# soldererboutdisplay.net
KiCad netlist of a schematic drawn in Altium Designer
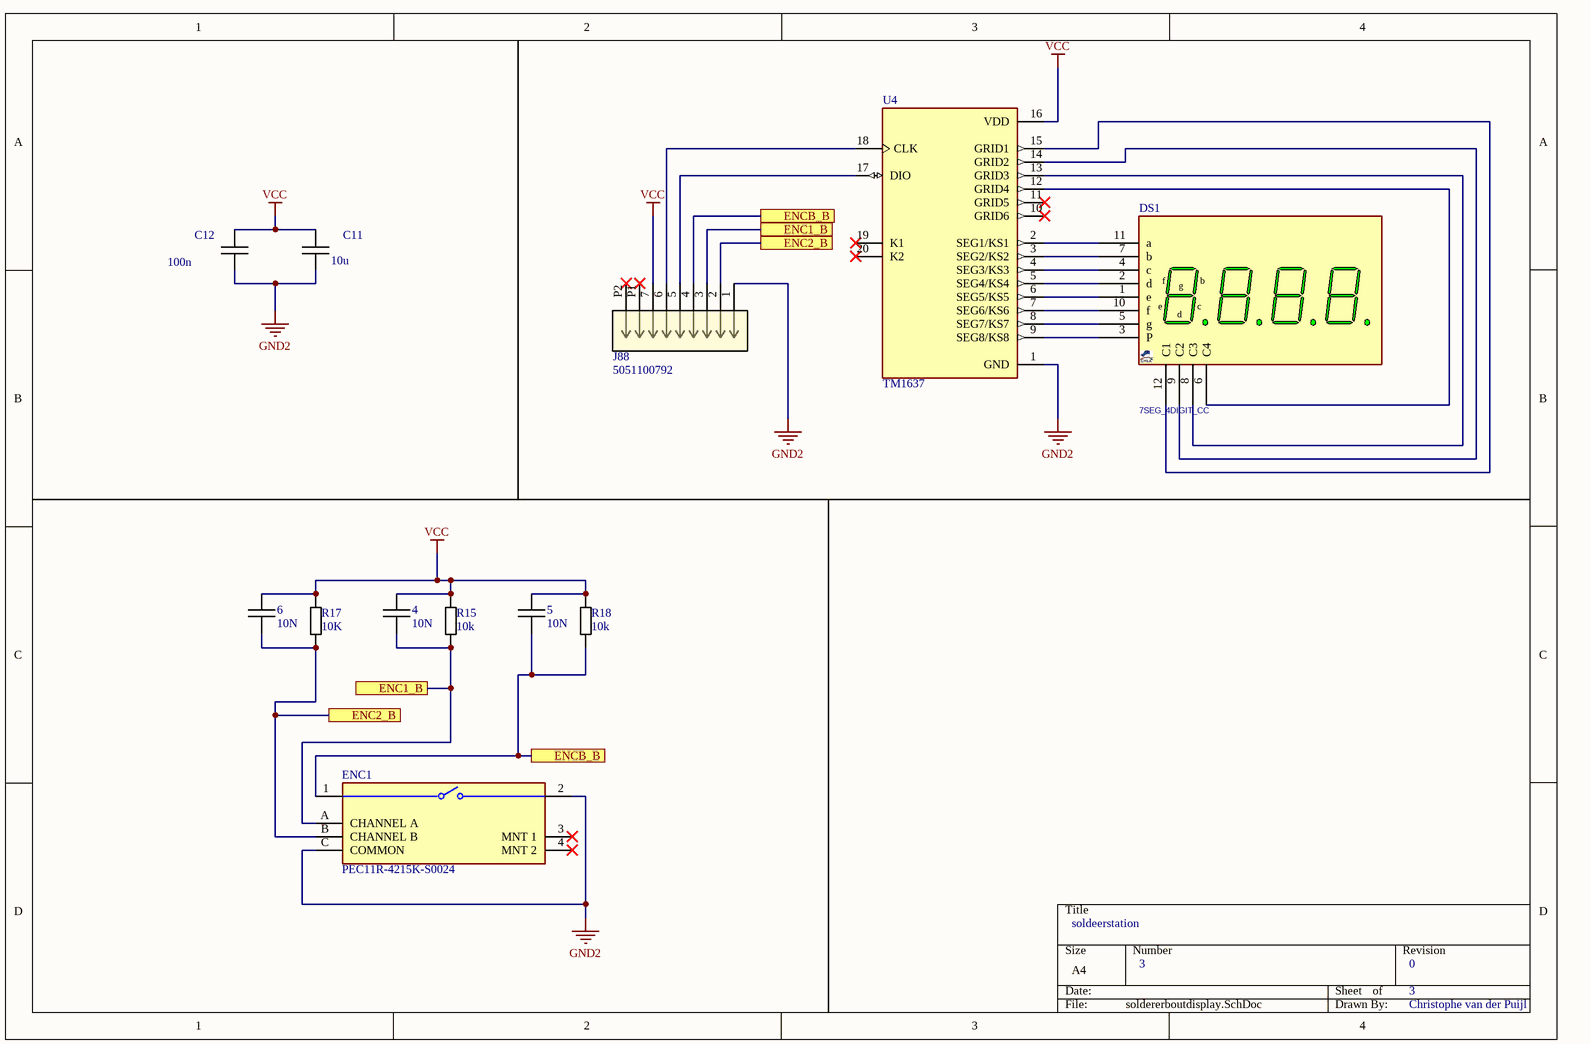
[diagram p0: soldererboutdisplay.SchDoc]

(export (version "E")
  (design (tool "Eeschema 10.0.6"))
  (components
    (comp (ref "4") (value "10N") (footprint "C 0603 / 1608") (libsource (lib "Standard") (part "Capacitor")))
    (comp (ref "5") (value "10N") (footprint "C 0603 / 1608") (libsource (lib "Standard") (part "Capacitor")))
    (comp (ref "6") (value "10N") (footprint "C 0603 / 1608") (libsource (lib "Standard") (part "Capacitor")))
    (comp (ref "C11")
      (value "10u")
      (footprint "C 0603 / 1608")
      (libsource (lib "Standard") (part "Capacitor"))
    )
    (comp (ref "C12")
      (value "100n")
      (footprint "C 0603 / 1608")
      (libsource (lib "Standard") (part "Capacitor"))
    )
    (comp (ref "DS1")
      (value "7SEG_4DIGIT_CC")
      (footprint "7SEGX4_12")
      (description "7SEGMENT, 4DIGIT, common cathode 5641")
      (fields (field (name "MANF_P#") "DPY-4CK"))
      (libsource (lib "Standard") (part "7SEG_4DIGIT_CC"))
    )
    (comp (ref "ENC1")
      (value "PEC11R-4215K-S0024")
      (footprint "FP-PEC11R-4215K-S0024-MFG")
      (description "ROTARY ENCODER MECHANICAL 24PPR")
      (libsource (lib "Standard") (part "pec11r425fs0024"))
    )
    (comp (ref "J88")
      (value "5051100792")
      (footprint "CON_5051100792_MOL")
      (description "No Description Available")
      (libsource (lib "Standard") (part "5051100792"))
    )
    (comp (ref "R15") (value "10k") (footprint "R 0603") (libsource (lib "Standard") (part "Resistor")))
    (comp (ref "R17") (value "10K") (footprint "R 0603") (libsource (lib "Standard") (part "Resistor")))
    (comp (ref "R18") (value "10k") (footprint "R 0603") (libsource (lib "Standard") (part "Resistor")))
    (comp (ref "U4")
      (value "TM1637")
      (footprint "DIP778W43P254L2612H431Q20N")
      (description "LED Drive Control Special Circuit")
      (fields (field (name "MF") "Titan Micro Electronics"))
      (libsource (lib "Standard") (part "TM1637"))
    )
  )
  (nets
    (net (code "1") (name "/ENC1_B") (class "Default")
      (node (ref "4") (pin "1") (pinfunction "1_1") (pintype "passive"))
      (node (ref "ENC1") (pin "A") (pinfunction "CHANNEL_A_A") (pintype "passive"))
      (node (ref "J88") (pin "3") (pinfunction "3_3") (pintype "passive"))
      (node (ref "R15") (pin "1") (pinfunction "1_1") (pintype "passive"))
    )
    (net (code "2") (name "/ENC2_B") (class "Default")
      (node (ref "6") (pin "1") (pinfunction "1_1") (pintype "passive"))
      (node (ref "ENC1") (pin "B") (pinfunction "CHANNEL_B_B") (pintype "passive"))
      (node (ref "J88") (pin "2") (pinfunction "2_2") (pintype "passive"))
      (node (ref "R17") (pin "1") (pinfunction "1_1") (pintype "passive"))
    )
    (net (code "3") (name "/ENCB_B") (class "Default")
      (node (ref "5") (pin "1") (pinfunction "1_1") (pintype "passive"))
      (node (ref "ENC1") (pin "1") (pinfunction "1_1") (pintype "passive"))
      (node (ref "J88") (pin "4") (pinfunction "4_4") (pintype "passive"))
      (node (ref "R18") (pin "1") (pinfunction "1_1") (pintype "passive"))
    )
    (net (code "4") (name "GND2") (class "Default")
      (node (ref "C11") (pin "2") (pinfunction "1_2") (pintype "passive"))
      (node (ref "C12") (pin "2") (pinfunction "1_2") (pintype "passive"))
      (node (ref "ENC1") (pin "2") (pinfunction "2_2") (pintype "passive"))
      (node (ref "ENC1") (pin "C") (pinfunction "COMMON_C") (pintype "passive"))
      (node (ref "J88") (pin "1") (pinfunction "1_1") (pintype "passive"))
      (node (ref "U4") (pin "1") (pinfunction "GND_1") (pintype "power_in"))
    )
    (net (code "5") (name "Net-(DS1-C1)") (class "Default")
      (node (ref "DS1") (pin "12") (pinfunction "C1_12") (pintype "passive"))
      (node (ref "U4") (pin "15") (pinfunction "GRID1_15") (pintype "output"))
    )
    (net (code "6") (name "Net-(DS1-C2)") (class "Default")
      (node (ref "DS1") (pin "9") (pinfunction "C2_9") (pintype "passive"))
      (node (ref "U4") (pin "14") (pinfunction "GRID2_14") (pintype "output"))
    )
    (net (code "7") (name "Net-(DS1-C3)") (class "Default")
      (node (ref "DS1") (pin "8") (pinfunction "C3_8") (pintype "passive"))
      (node (ref "U4") (pin "13") (pinfunction "GRID3_13") (pintype "output"))
    )
    (net (code "8") (name "Net-(DS1-C4)") (class "Default")
      (node (ref "DS1") (pin "6") (pinfunction "C4_6") (pintype "passive"))
      (node (ref "U4") (pin "12") (pinfunction "GRID4_12") (pintype "output"))
    )
    (net (code "9") (name "Net-(DS1-P)") (class "Default")
      (node (ref "DS1") (pin "3") (pinfunction "P_3") (pintype "passive"))
      (node (ref "U4") (pin "9") (pinfunction "SEG8/KS8_9") (pintype "output"))
    )
    (net (code "10") (name "Net-(DS1-a)") (class "Default")
      (node (ref "DS1") (pin "11") (pinfunction "a_11") (pintype "passive"))
      (node (ref "U4") (pin "2") (pinfunction "SEG1/KS1_2") (pintype "output"))
    )
    (net (code "11") (name "Net-(DS1-b)") (class "Default")
      (node (ref "DS1") (pin "7") (pinfunction "b_7") (pintype "passive"))
      (node (ref "U4") (pin "3") (pinfunction "SEG2/KS2_3") (pintype "output"))
    )
    (net (code "12") (name "Net-(DS1-c)") (class "Default")
      (node (ref "DS1") (pin "4") (pinfunction "c_4") (pintype "passive"))
      (node (ref "U4") (pin "4") (pinfunction "SEG3/KS3_4") (pintype "output"))
    )
    (net (code "13") (name "Net-(DS1-d)") (class "Default")
      (node (ref "DS1") (pin "2") (pinfunction "d_2") (pintype "passive"))
      (node (ref "U4") (pin "5") (pinfunction "SEG4/KS4_5") (pintype "output"))
    )
    (net (code "14") (name "Net-(DS1-e)") (class "Default")
      (node (ref "DS1") (pin "1") (pinfunction "e_1") (pintype "passive"))
      (node (ref "U4") (pin "6") (pinfunction "SEG5/KS5_6") (pintype "output"))
    )
    (net (code "15") (name "Net-(DS1-f)") (class "Default")
      (node (ref "DS1") (pin "10") (pinfunction "f_10") (pintype "passive"))
      (node (ref "U4") (pin "7") (pinfunction "SEG6/KS6_7") (pintype "output"))
    )
    (net (code "16") (name "Net-(DS1-g)") (class "Default")
      (node (ref "DS1") (pin "5") (pinfunction "g_5") (pintype "passive"))
      (node (ref "U4") (pin "8") (pinfunction "SEG7/KS7_8") (pintype "output"))
    )
    (net (code "17") (name "Net-(U4-CLK)") (class "Default")
      (node (ref "J88") (pin "6") (pinfunction "6_6") (pintype "passive"))
      (node (ref "U4") (pin "18") (pinfunction "CLK_18") (pintype "passive"))
    )
    (net (code "18") (name "Net-(U4-DIO)") (class "Default")
      (node (ref "J88") (pin "5") (pinfunction "5_5") (pintype "passive"))
      (node (ref "U4") (pin "17") (pinfunction "DIO_17") (pintype "bidirectional"))
    )
    (net (code "19") (name "VCC") (class "Default")
      (node (ref "4") (pin "2") (pinfunction "1_2") (pintype "passive"))
      (node (ref "5") (pin "2") (pinfunction "1_2") (pintype "passive"))
      (node (ref "6") (pin "2") (pinfunction "1_2") (pintype "passive"))
      (node (ref "C11") (pin "1") (pinfunction "1_1") (pintype "passive"))
      (node (ref "C12") (pin "1") (pinfunction "1_1") (pintype "passive"))
      (node (ref "J88") (pin "7") (pinfunction "7_7") (pintype "passive"))
      (node (ref "R15") (pin "2") (pinfunction "2_2") (pintype "passive"))
      (node (ref "R17") (pin "2") (pinfunction "2_2") (pintype "passive"))
      (node (ref "R18") (pin "2") (pinfunction "2_2") (pintype "passive"))
      (node (ref "U4") (pin "16") (pinfunction "VDD_16") (pintype "power_in"))
    )
    (net (code "20") (name "unconnected-(ENC1-MNT_1-Pad3)") (class "Default")
      (node (ref "ENC1") (pin "3") (pinfunction "MNT_1_3") (pintype "passive+no_connect"))
    )
    (net (code "21") (name "unconnected-(ENC1-MNT_2-Pad4)") (class "Default")
      (node (ref "ENC1") (pin "4") (pinfunction "MNT_2_4") (pintype "passive+no_connect"))
    )
    (net (code "22") (name "unconnected-(J88-PadP1)") (class "Default")
      (node (ref "J88") (pin "P1") (pinfunction "P1_P1") (pintype "passive+no_connect"))
    )
    (net (code "23") (name "unconnected-(J88-PadP2)") (class "Default")
      (node (ref "J88") (pin "P2") (pinfunction "P2_P2") (pintype "passive+no_connect"))
    )
    (net (code "24") (name "unconnected-(U4-GRID5-Pad11)") (class "Default")
      (node (ref "U4") (pin "11") (pinfunction "GRID5_11") (pintype "output+no_connect"))
    )
    (net (code "25") (name "unconnected-(U4-GRID6-Pad10)") (class "Default")
      (node (ref "U4") (pin "10") (pinfunction "GRID6_10") (pintype "output+no_connect"))
    )
    (net (code "26") (name "unconnected-(U4-K1-Pad19)") (class "Default")
      (node (ref "U4") (pin "19") (pinfunction "K1_19") (pintype "passive+no_connect"))
    )
    (net (code "27") (name "unconnected-(U4-K2-Pad20)") (class "Default")
      (node (ref "U4") (pin "20") (pinfunction "K2_20") (pintype "passive+no_connect"))
    )
  )
)
